# FSM.net
KiCad netlist of a schematic drawn in Altium Designer
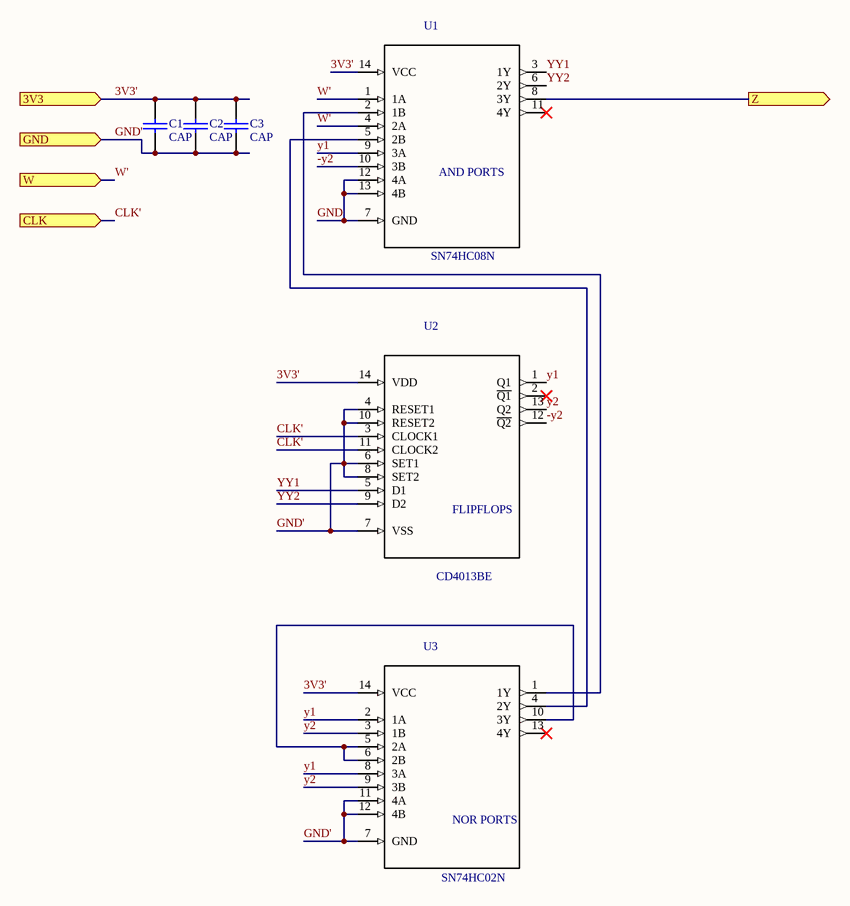
[diagram p0: FSM.SchDoc]

(export (version "E")
  (design (tool "Eeschema 10.0.6"))
  (components
    (comp (ref "C1") (value "CAP") (footprint "0805") (libsource (lib "LIBEBAL") (part "CAP")))
    (comp (ref "C2") (value "CAP") (footprint "0805") (libsource (lib "LIBEBAL") (part "CAP")))
    (comp (ref "C3") (value "CAP") (footprint "0805") (libsource (lib "LIBEBAL") (part "CAP")))
    (comp (ref "U1")
      (value "SN74HC08N")
      (footprint "*DIP254P762X508-14")
      (description "AND Gate 4-Element 2-IN CMOS 14-Pin PDIP Tube")
      (fields (field (name "MF") "Texas Instruments"))
      (libsource (lib "SN74HC08N") (part "SN74HC08N"))
    )
    (comp (ref "U2")
      (value "CD4013BE")
      (footprint "*DIP254P762X508-14")
      (description "Flip Flop D-Type Pos-Edge 2-Element 14-Pin PDIP")
      (fields (field (name "MF") "Texas"))
      (libsource (lib "CD4013BE") (part "CD4013BE"))
    )
    (comp (ref "U3")
      (value "SN74HC02N")
      (footprint "*DIP254P762X508-14")
      (description "IC: digital; Channels: 4; NOR; Inputs: 2; THT; DIP14; Ser")
      (fields (field (name "MF") "Texas Instruments"))
      (libsource (lib "SN74HC02N") (part "SN74HC02N"))
    )
  )
  (nets
    (net (code "1") (name "/-y2") (class "Default")
      (node (ref "U1") (pin "10") (pinfunction "3B_10") (pintype "input"))
      (node (ref "U2") (pin "12") (pinfunction "~{Q2}_12") (pintype "output"))
    )
    (net (code "2") (name "/3V3'") (class "Default")
      (node (ref "C1") (pin "1") (pinfunction "1_1") (pintype "passive"))
      (node (ref "C2") (pin "1") (pinfunction "1_1") (pintype "passive"))
      (node (ref "C3") (pin "1") (pinfunction "1_1") (pintype "passive"))
      (node (ref "U1") (pin "14") (pinfunction "VCC_14") (pintype "input"))
      (node (ref "U2") (pin "14") (pinfunction "VDD_14") (pintype "input"))
      (node (ref "U3") (pin "14") (pinfunction "VCC_14") (pintype "input"))
    )
    (net (code "3") (name "/CLK'") (class "Default")
      (node (ref "U2") (pin "11") (pinfunction "CLOCK2_11") (pintype "input"))
      (node (ref "U2") (pin "3") (pinfunction "CLOCK1_3") (pintype "input"))
    )
    (net (code "4") (name "/GND'") (class "Default")
      (node (ref "C1") (pin "2") (pinfunction "2_2") (pintype "passive"))
      (node (ref "C2") (pin "2") (pinfunction "2_2") (pintype "passive"))
      (node (ref "C3") (pin "2") (pinfunction "2_2") (pintype "passive"))
      (node (ref "U1") (pin "12") (pinfunction "4A_12") (pintype "input"))
      (node (ref "U1") (pin "13") (pinfunction "4B_13") (pintype "input"))
      (node (ref "U1") (pin "7") (pinfunction "GND_7") (pintype "input"))
      (node (ref "U2") (pin "10") (pinfunction "RESET2_10") (pintype "input"))
      (node (ref "U2") (pin "4") (pinfunction "RESET1_4") (pintype "input"))
      (node (ref "U2") (pin "6") (pinfunction "SET1_6") (pintype "input"))
      (node (ref "U2") (pin "7") (pinfunction "VSS_7") (pintype "input"))
      (node (ref "U2") (pin "8") (pinfunction "SET2_8") (pintype "input"))
      (node (ref "U3") (pin "11") (pinfunction "4A_11") (pintype "input"))
      (node (ref "U3") (pin "12") (pinfunction "4B_12") (pintype "input"))
      (node (ref "U3") (pin "7") (pinfunction "GND_7") (pintype "input"))
    )
    (net (code "5") (name "/W'") (class "Default")
      (node (ref "U1") (pin "1") (pinfunction "1A_1") (pintype "input"))
      (node (ref "U1") (pin "4") (pinfunction "2A_4") (pintype "input"))
    )
    (net (code "6") (name "/YY1") (class "Default")
      (node (ref "U1") (pin "3") (pinfunction "1Y_3") (pintype "output"))
      (node (ref "U2") (pin "5") (pinfunction "D1_5") (pintype "input"))
    )
    (net (code "7") (name "/YY2") (class "Default")
      (node (ref "U1") (pin "6") (pinfunction "2Y_6") (pintype "output"))
      (node (ref "U2") (pin "9") (pinfunction "D2_9") (pintype "input"))
    )
    (net (code "8") (name "/Z") (class "Default")
      (node (ref "U1") (pin "8") (pinfunction "3Y_8") (pintype "output"))
    )
    (net (code "9") (name "/y1") (class "Default")
      (node (ref "U1") (pin "9") (pinfunction "3A_9") (pintype "input"))
      (node (ref "U2") (pin "1") (pinfunction "Q1_1") (pintype "output"))
      (node (ref "U3") (pin "2") (pinfunction "1A_2") (pintype "input"))
      (node (ref "U3") (pin "8") (pinfunction "3A_8") (pintype "input"))
    )
    (net (code "10") (name "/y2") (class "Default")
      (node (ref "U2") (pin "13") (pinfunction "Q2_13") (pintype "output"))
      (node (ref "U3") (pin "3") (pinfunction "1B_3") (pintype "input"))
      (node (ref "U3") (pin "9") (pinfunction "3B_9") (pintype "input"))
    )
    (net (code "11") (name "Net-(U1-1B)") (class "Default")
      (node (ref "U1") (pin "2") (pinfunction "1B_2") (pintype "input"))
      (node (ref "U3") (pin "1") (pinfunction "1Y_1") (pintype "output"))
    )
    (net (code "12") (name "Net-(U1-2B)") (class "Default")
      (node (ref "U1") (pin "5") (pinfunction "2B_5") (pintype "input"))
      (node (ref "U3") (pin "4") (pinfunction "2Y_4") (pintype "output"))
    )
    (net (code "13") (name "Net-(U3-2A)") (class "Default")
      (node (ref "U3") (pin "10") (pinfunction "3Y_10") (pintype "output"))
      (node (ref "U3") (pin "5") (pinfunction "2A_5") (pintype "input"))
      (node (ref "U3") (pin "6") (pinfunction "2B_6") (pintype "input"))
    )
    (net (code "14") (name "unconnected-(U1-4Y-Pad11)") (class "Default")
      (node (ref "U1") (pin "11") (pinfunction "4Y_11") (pintype "output+no_connect"))
    )
    (net (code "15") (name "unconnected-(U2-~{Q1}-Pad2)") (class "Default")
      (node (ref "U2") (pin "2") (pinfunction "~{Q1}_2") (pintype "output+no_connect"))
    )
    (net (code "16") (name "unconnected-(U3-4Y-Pad13)") (class "Default")
      (node (ref "U3") (pin "13") (pinfunction "4Y_13") (pintype "output+no_connect"))
    )
  )
)
